# board_final.net
KiCad netlist of a schematic drawn in EAGLE
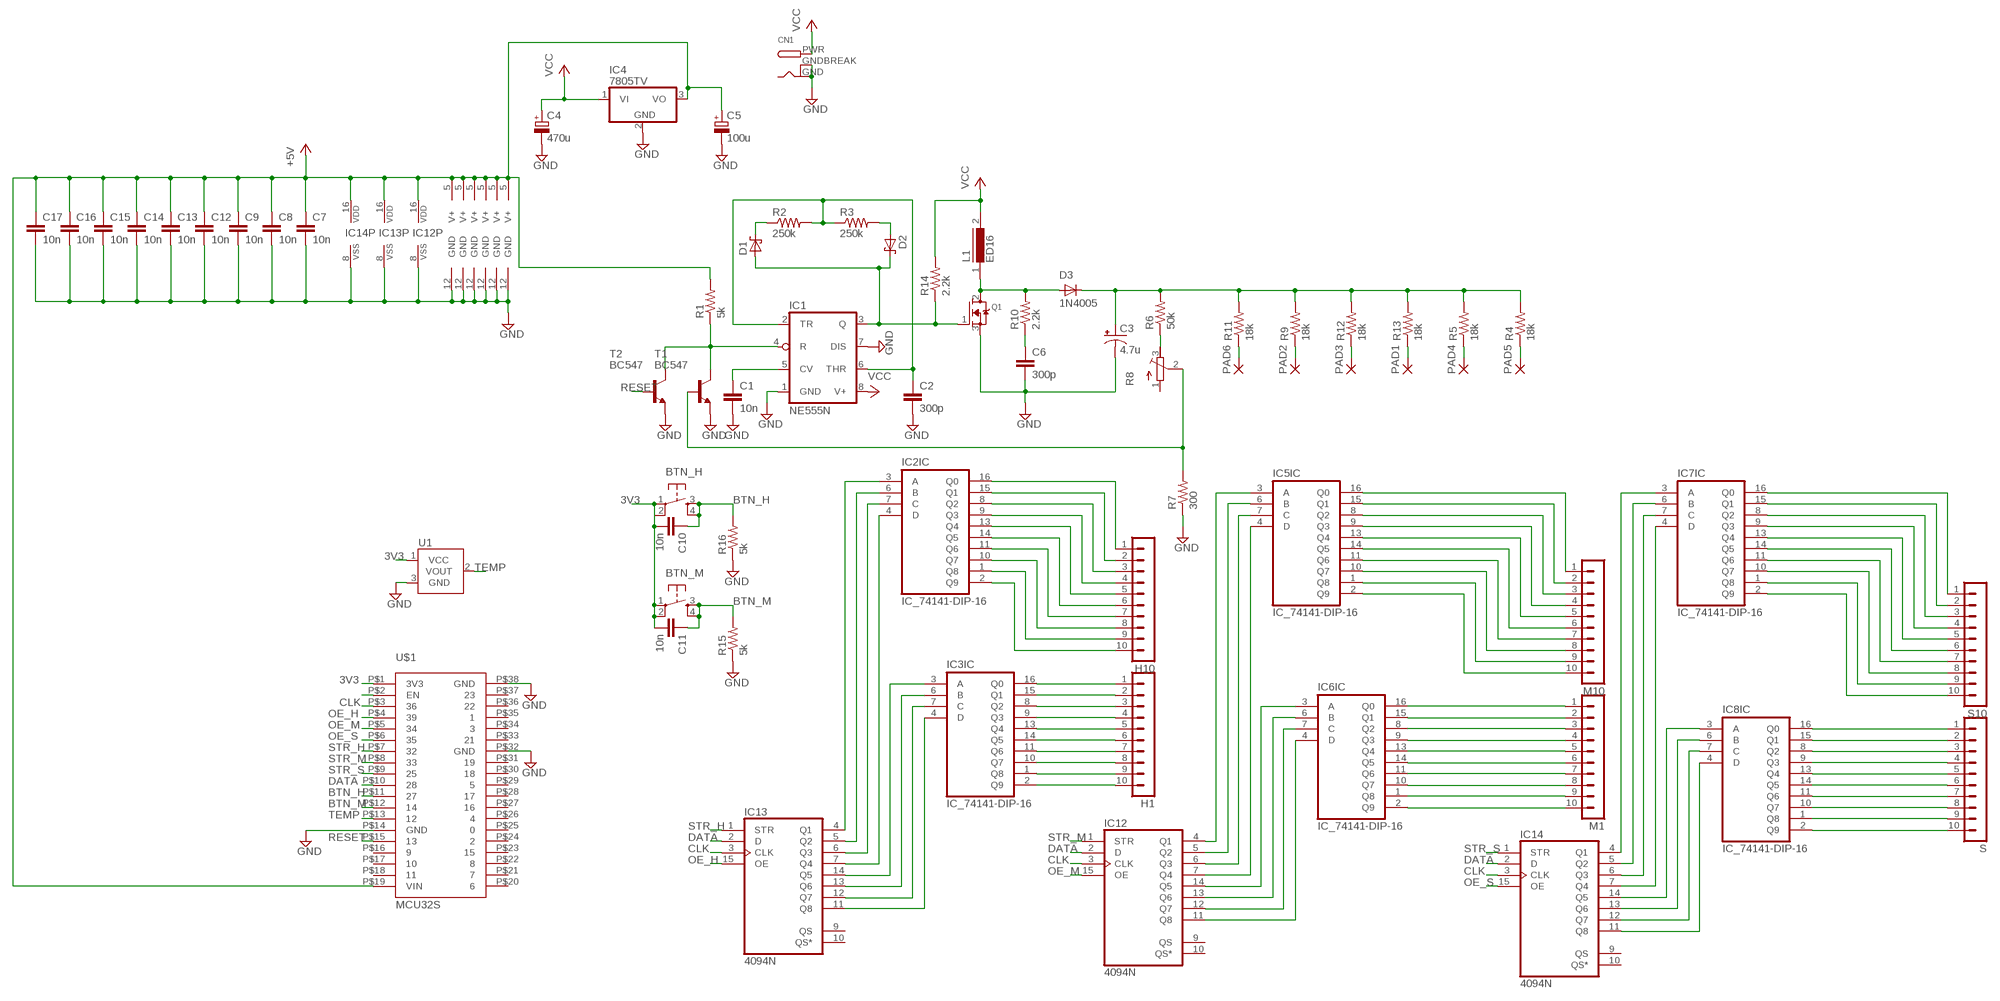
[diagram p0: schematic, sheet 1]

(export (version "E")
  (design (tool "Eeschema 10.0.6"))
  (components
    (comp (ref "BTN_H")
      (value "TAC_SWITCHPTH")
      (footprint "eagle-import:TACTILE-PTH")
      (libsource (lib "eagle-import") (part "TAC_SWITCHPTH"))
    )
    (comp (ref "BTN_M")
      (value "TAC_SWITCHPTH")
      (footprint "eagle-import:TACTILE-PTH")
      (libsource (lib "eagle-import") (part "TAC_SWITCHPTH"))
    )
    (comp (ref "C1")
      (value "10n")
      (footprint "eagle-import:C050-030X075")
      (libsource (lib "eagle-import") (part "C-EU050-030X075"))
    )
    (comp (ref "C2")
      (value "300p")
      (footprint "eagle-import:C050-030X075")
      (libsource (lib "eagle-import") (part "C-EU050-030X075"))
    )
    (comp (ref "C3")
      (value "4.7u")
      (footprint "eagle-import:E3,5-10")
      (libsource (lib "eagle-import") (part "CPOL-USE3.5-10"))
    )
    (comp (ref "C4")
      (value "470u")
      (footprint "eagle-import:E5-8,5")
      (libsource (lib "eagle-import") (part "CPOL-EUE5-8.5"))
    )
    (comp (ref "C5")
      (value "100u")
      (footprint "eagle-import:E5-8,5")
      (libsource (lib "eagle-import") (part "CPOL-EUE5-8.5"))
    )
    (comp (ref "C6")
      (value "300p")
      (footprint "eagle-import:C050-030X075")
      (libsource (lib "eagle-import") (part "C-EU050-030X075"))
    )
    (comp (ref "C7")
      (value "10n")
      (footprint "eagle-import:C050-030X075")
      (libsource (lib "eagle-import") (part "C-EU050-030X075"))
    )
    (comp (ref "C8")
      (value "10n")
      (footprint "eagle-import:C050-030X075")
      (libsource (lib "eagle-import") (part "C-EU050-030X075"))
    )
    (comp (ref "C9")
      (value "10n")
      (footprint "eagle-import:C050-030X075")
      (libsource (lib "eagle-import") (part "C-EU050-030X075"))
    )
    (comp (ref "C10")
      (value "10n")
      (footprint "eagle-import:C050-030X075")
      (libsource (lib "eagle-import") (part "C-EU050-030X075"))
    )
    (comp (ref "C11")
      (value "10n")
      (footprint "eagle-import:C050-030X075")
      (libsource (lib "eagle-import") (part "C-EU050-030X075"))
    )
    (comp (ref "C12")
      (value "10n")
      (footprint "eagle-import:C050-030X075")
      (libsource (lib "eagle-import") (part "C-EU050-030X075"))
    )
    (comp (ref "C13")
      (value "10n")
      (footprint "eagle-import:C050-030X075")
      (libsource (lib "eagle-import") (part "C-EU050-030X075"))
    )
    (comp (ref "C14")
      (value "10n")
      (footprint "eagle-import:C050-030X075")
      (libsource (lib "eagle-import") (part "C-EU050-030X075"))
    )
    (comp (ref "C15")
      (value "10n")
      (footprint "eagle-import:C050-030X075")
      (libsource (lib "eagle-import") (part "C-EU050-030X075"))
    )
    (comp (ref "C16")
      (value "10n")
      (footprint "eagle-import:C050-030X075")
      (libsource (lib "eagle-import") (part "C-EU050-030X075"))
    )
    (comp (ref "C17")
      (value "10n")
      (footprint "eagle-import:C050-030X075")
      (libsource (lib "eagle-import") (part "C-EU050-030X075"))
    )
    (comp (ref "CN1")
      (value "DCBARRELPTH")
      (footprint "eagle-import:DCJACK_2MM_PTH")
      (libsource (lib "eagle-import") (part "DCBARRELPTH"))
    )
    (comp (ref "D1")
      (value "SCHOTTKY-DIODEF126Z12")
      (footprint "eagle-import:F126Z12")
      (libsource (lib "eagle-import") (part "SCHOTTKY-DIODEF126Z12"))
    )
    (comp (ref "D2")
      (value "SCHOTTKY-DIODEF126Z12")
      (footprint "eagle-import:F126Z12")
      (libsource (lib "eagle-import") (part "SCHOTTKY-DIODEF126Z12"))
    )
    (comp (ref "D3")
      (value "1N4005")
      (footprint "eagle-import:DO41-10")
      (libsource (lib "eagle-import") (part "1N4005"))
    )
    (comp (ref "H1")
      (value "MA10-1")
      (footprint "eagle-import:MA10-1")
      (libsource (lib "eagle-import") (part "MA10-1"))
    )
    (comp (ref "H10")
      (value "MA10-1")
      (footprint "eagle-import:MA10-1")
      (libsource (lib "eagle-import") (part "MA10-1"))
    )
    (comp (ref "IC1")
      (value "NE555N")
      (footprint "eagle-import:DIL08")
      (libsource (lib "eagle-import") (part "555NNE"))
    )
    (comp (ref "IC2")
      (value "IC_74141-DIP-16")
      (footprint "eagle-import:DIL16")
      (libsource (lib "eagle-import") (part "IC_74141-DIP-16"))
    )
    (comp (ref "IC3")
      (value "IC_74141-DIP-16")
      (footprint "eagle-import:DIL16")
      (libsource (lib "eagle-import") (part "IC_74141-DIP-16"))
    )
    (comp (ref "IC4")
      (value "7805TV")
      (footprint "eagle-import:TO220V")
      (libsource (lib "eagle-import") (part "78TV05"))
    )
    (comp (ref "IC5")
      (value "IC_74141-DIP-16")
      (footprint "eagle-import:DIL16")
      (libsource (lib "eagle-import") (part "IC_74141-DIP-16"))
    )
    (comp (ref "IC6")
      (value "IC_74141-DIP-16")
      (footprint "eagle-import:DIL16")
      (libsource (lib "eagle-import") (part "IC_74141-DIP-16"))
    )
    (comp (ref "IC7")
      (value "IC_74141-DIP-16")
      (footprint "eagle-import:DIL16")
      (libsource (lib "eagle-import") (part "IC_74141-DIP-16"))
    )
    (comp (ref "IC8")
      (value "IC_74141-DIP-16")
      (footprint "eagle-import:DIL16")
      (libsource (lib "eagle-import") (part "IC_74141-DIP-16"))
    )
    (comp (ref "IC12")
      (value "4094N")
      (footprint "eagle-import:DIL16")
      (libsource (lib "eagle-import") (part "4094N"))
    )
    (comp (ref "IC13")
      (value "4094N")
      (footprint "eagle-import:DIL16")
      (libsource (lib "eagle-import") (part "4094N"))
    )
    (comp (ref "IC14")
      (value "4094N")
      (footprint "eagle-import:DIL16")
      (libsource (lib "eagle-import") (part "4094N"))
    )
    (comp (ref "L1")
      (value "ED16")
      (footprint "eagle-import:ED16")
      (libsource (lib "eagle-import") (part "ED16"))
    )
    (comp (ref "M1")
      (value "MA10-1")
      (footprint "eagle-import:MA10-1")
      (libsource (lib "eagle-import") (part "MA10-1"))
    )
    (comp (ref "M10")
      (value "MA10-1")
      (footprint "eagle-import:MA10-1")
      (libsource (lib "eagle-import") (part "MA10-1"))
    )
    (comp (ref "PAD1")
      (value "3,17/1,3")
      (footprint "eagle-import:3,17_1,3")
      (libsource (lib "eagle-import") (part "3,17/1,3"))
    )
    (comp (ref "PAD2")
      (value "3,17/1,3")
      (footprint "eagle-import:3,17_1,3")
      (libsource (lib "eagle-import") (part "3,17/1,3"))
    )
    (comp (ref "PAD3")
      (value "3,17/1,3")
      (footprint "eagle-import:3,17_1,3")
      (libsource (lib "eagle-import") (part "3,17/1,3"))
    )
    (comp (ref "PAD4")
      (value "3,17/1,3")
      (footprint "eagle-import:3,17_1,3")
      (libsource (lib "eagle-import") (part "3,17/1,3"))
    )
    (comp (ref "PAD5")
      (value "3,17/1,3")
      (footprint "eagle-import:3,17_1,3")
      (libsource (lib "eagle-import") (part "3,17/1,3"))
    )
    (comp (ref "PAD6")
      (value "3,17/1,3")
      (footprint "eagle-import:3,17_1,3")
      (libsource (lib "eagle-import") (part "3,17/1,3"))
    )
    (comp (ref "Q1")
      (value "MOSFET-NGDS_TO220V")
      (footprint "eagle-import:TO220V")
      (libsource (lib "eagle-import") (part "MOSFET-NGDS_TO220V"))
    )
    (comp (ref "R1")
      (value "5k")
      (footprint "eagle-import:0207_10")
      (libsource (lib "eagle-import") (part "R-US_0207/10"))
    )
    (comp (ref "R2")
      (value "250k")
      (footprint "eagle-import:0207_10")
      (libsource (lib "eagle-import") (part "R-US_0207/10"))
    )
    (comp (ref "R3")
      (value "250k")
      (footprint "eagle-import:0207_10")
      (libsource (lib "eagle-import") (part "R-US_0207/10"))
    )
    (comp (ref "R4")
      (value "18k")
      (footprint "eagle-import:0207_10")
      (libsource (lib "eagle-import") (part "R-US_0207/10"))
    )
    (comp (ref "R5")
      (value "18k")
      (footprint "eagle-import:0207_10")
      (libsource (lib "eagle-import") (part "R-US_0207/10"))
    )
    (comp (ref "R6")
      (value "50k")
      (footprint "eagle-import:0207_10")
      (libsource (lib "eagle-import") (part "R-US_0207/10"))
    )
    (comp (ref "R7")
      (value "300")
      (footprint "eagle-import:0207_10")
      (libsource (lib "eagle-import") (part "R-US_0207/10"))
    )
    (comp (ref "R8")
      (value "R-TRIMM3296W")
      (footprint "eagle-import:RTRIM3296W")
      (libsource (lib "eagle-import") (part "R-TRIMM3296W"))
    )
    (comp (ref "R9")
      (value "18k")
      (footprint "eagle-import:0207_10")
      (libsource (lib "eagle-import") (part "R-US_0207/10"))
    )
    (comp (ref "R10")
      (value "2.2k")
      (footprint "eagle-import:0207_10")
      (libsource (lib "eagle-import") (part "R-US_0207/10"))
    )
    (comp (ref "R11")
      (value "18k")
      (footprint "eagle-import:0207_10")
      (libsource (lib "eagle-import") (part "R-US_0207/10"))
    )
    (comp (ref "R12")
      (value "18k")
      (footprint "eagle-import:0207_10")
      (libsource (lib "eagle-import") (part "R-US_0207/10"))
    )
    (comp (ref "R13")
      (value "18k")
      (footprint "eagle-import:0207_10")
      (libsource (lib "eagle-import") (part "R-US_0207/10"))
    )
    (comp (ref "R14")
      (value "2.2k")
      (footprint "eagle-import:0207_10")
      (libsource (lib "eagle-import") (part "R-US_0207/10"))
    )
    (comp (ref "R15")
      (value "5k")
      (footprint "eagle-import:0207_10")
      (libsource (lib "eagle-import") (part "R-US_0207/10"))
    )
    (comp (ref "R16")
      (value "5k")
      (footprint "eagle-import:0207_10")
      (libsource (lib "eagle-import") (part "R-US_0207/10"))
    )
    (comp (ref "S")
      (value "MA10-1")
      (footprint "eagle-import:MA10-1")
      (libsource (lib "eagle-import") (part "MA10-1"))
    )
    (comp (ref "S10")
      (value "MA10-1")
      (footprint "eagle-import:MA10-1")
      (libsource (lib "eagle-import") (part "MA10-1"))
    )
    (comp (ref "T1")
      (value "BC547")
      (footprint "eagle-import:TO92")
      (libsource (lib "eagle-import") (part "BC547"))
    )
    (comp (ref "T2")
      (value "BC547")
      (footprint "eagle-import:TO92")
      (libsource (lib "eagle-import") (part "BC547"))
    )
    (comp (ref "U$1")
      (value "MCU32S")
      (footprint "eagle-import:NODEMCU32S")
      (libsource (lib "eagle-import") (part "MCU32S"))
    )
    (comp (ref "U1")
      (value "TMP36GT9")
      (footprint "eagle-import:TO-92")
      (libsource (lib "eagle-import") (part "TMP36GT9"))
    )
  )
  (nets
    (net (code "1") (name "+5V") (class "Default")
      (node (ref "C12") (pin "1") (pinfunction "1_1") (pintype "passive"))
      (node (ref "C13") (pin "1") (pinfunction "1_1") (pintype "passive"))
      (node (ref "C14") (pin "1") (pinfunction "1_1") (pintype "passive"))
      (node (ref "C15") (pin "1") (pinfunction "1_1") (pintype "passive"))
      (node (ref "C16") (pin "1") (pinfunction "1_1") (pintype "passive"))
      (node (ref "C17") (pin "1") (pinfunction "1_1") (pintype "passive"))
      (node (ref "C5") (pin "+") (pinfunction "+_+") (pintype "passive"))
      (node (ref "C7") (pin "1") (pinfunction "1_1") (pintype "passive"))
      (node (ref "C8") (pin "1") (pinfunction "1_1") (pintype "passive"))
      (node (ref "C9") (pin "1") (pinfunction "1_1") (pintype "passive"))
      (node (ref "IC12") (pin "16") (pinfunction "VDD_16") (pintype "power_in"))
      (node (ref "IC13") (pin "16") (pinfunction "VDD_16") (pintype "power_in"))
      (node (ref "IC14") (pin "16") (pinfunction "VDD_16") (pintype "power_in"))
      (node (ref "IC2") (pin "5") (pinfunction "V+_5") (pintype "power_in"))
      (node (ref "IC3") (pin "5") (pinfunction "V+_5") (pintype "power_in"))
      (node (ref "IC4") (pin "3") (pinfunction "VO_3") (pintype "passive"))
      (node (ref "IC5") (pin "5") (pinfunction "V+_5") (pintype "power_in"))
      (node (ref "IC6") (pin "5") (pinfunction "V+_5") (pintype "power_in"))
      (node (ref "IC7") (pin "5") (pinfunction "V+_5") (pintype "power_in"))
      (node (ref "IC8") (pin "5") (pinfunction "V+_5") (pintype "power_in"))
      (node (ref "R1") (pin "2") (pinfunction "2_2") (pintype "passive"))
      (node (ref "U$1") (pin "P$19") (pinfunction "VIN_P$19") (pintype "bidirectional"))
    )
    (net (code "2") (name "/3V3") (class "Default")
      (node (ref "BTN_H") (pin "1") (pinfunction "1_1") (pintype "passive"))
      (node (ref "BTN_H") (pin "2") (pinfunction "2_2") (pintype "passive"))
      (node (ref "BTN_M") (pin "1") (pinfunction "1_1") (pintype "passive"))
      (node (ref "BTN_M") (pin "2") (pinfunction "2_2") (pintype "passive"))
      (node (ref "C10") (pin "2") (pinfunction "2_2") (pintype "passive"))
      (node (ref "C11") (pin "2") (pinfunction "2_2") (pintype "passive"))
      (node (ref "U$1") (pin "P$1") (pinfunction "3V3_P$1") (pintype "bidirectional"))
      (node (ref "U1") (pin "1") (pinfunction "VCC_1") (pintype "bidirectional"))
    )
    (net (code "3") (name "/BTN_H") (class "Default")
      (node (ref "BTN_H") (pin "3") (pinfunction "3_3") (pintype "passive"))
      (node (ref "BTN_H") (pin "4") (pinfunction "4_4") (pintype "passive"))
      (node (ref "C10") (pin "1") (pinfunction "1_1") (pintype "passive"))
      (node (ref "R16") (pin "2") (pinfunction "2_2") (pintype "passive"))
      (node (ref "U$1") (pin "P$11") (pinfunction "27_P$11") (pintype "bidirectional"))
    )
    (net (code "4") (name "/BTN_M") (class "Default")
      (node (ref "BTN_M") (pin "3") (pinfunction "3_3") (pintype "passive"))
      (node (ref "BTN_M") (pin "4") (pinfunction "4_4") (pintype "passive"))
      (node (ref "C11") (pin "1") (pinfunction "1_1") (pintype "passive"))
      (node (ref "R15") (pin "2") (pinfunction "2_2") (pintype "passive"))
      (node (ref "U$1") (pin "P$12") (pinfunction "14_P$12") (pintype "bidirectional"))
    )
    (net (code "5") (name "/CLK") (class "Default")
      (node (ref "IC12") (pin "3") (pinfunction "CLK_3") (pintype "input"))
      (node (ref "IC13") (pin "3") (pinfunction "CLK_3") (pintype "input"))
      (node (ref "IC14") (pin "3") (pinfunction "CLK_3") (pintype "input"))
      (node (ref "U$1") (pin "P$3") (pinfunction "36_P$3") (pintype "bidirectional"))
    )
    (net (code "6") (name "/DATA") (class "Default")
      (node (ref "IC12") (pin "2") (pinfunction "D_2") (pintype "input"))
      (node (ref "IC13") (pin "2") (pinfunction "D_2") (pintype "input"))
      (node (ref "IC14") (pin "2") (pinfunction "D_2") (pintype "input"))
      (node (ref "U$1") (pin "P$10") (pinfunction "28_P$10") (pintype "bidirectional"))
    )
    (net (code "7") (name "/OE_H") (class "Default")
      (node (ref "IC13") (pin "15") (pinfunction "OE_15") (pintype "input"))
      (node (ref "U$1") (pin "P$4") (pinfunction "39_P$4") (pintype "bidirectional"))
    )
    (net (code "8") (name "/OE_M") (class "Default")
      (node (ref "IC12") (pin "15") (pinfunction "OE_15") (pintype "input"))
      (node (ref "U$1") (pin "P$5") (pinfunction "34_P$5") (pintype "bidirectional"))
    )
    (net (code "9") (name "/OE_S") (class "Default")
      (node (ref "IC14") (pin "15") (pinfunction "OE_15") (pintype "input"))
      (node (ref "U$1") (pin "P$6") (pinfunction "35_P$6") (pintype "bidirectional"))
    )
    (net (code "10") (name "/RESET") (class "Default")
      (node (ref "T2") (pin "2") (pinfunction "B_2") (pintype "passive"))
      (node (ref "U$1") (pin "P$15") (pinfunction "13_P$15") (pintype "bidirectional"))
    )
    (net (code "11") (name "/STR_H") (class "Default")
      (node (ref "IC13") (pin "1") (pinfunction "STR_1") (pintype "input"))
      (node (ref "U$1") (pin "P$7") (pinfunction "32_P$7") (pintype "bidirectional"))
    )
    (net (code "12") (name "/STR_M") (class "Default")
      (node (ref "IC12") (pin "1") (pinfunction "STR_1") (pintype "input"))
      (node (ref "U$1") (pin "P$8") (pinfunction "33_P$8") (pintype "bidirectional"))
    )
    (net (code "13") (name "/STR_S") (class "Default")
      (node (ref "IC14") (pin "1") (pinfunction "STR_1") (pintype "input"))
      (node (ref "U$1") (pin "P$9") (pinfunction "25_P$9") (pintype "bidirectional"))
    )
    (net (code "14") (name "/TEMP") (class "Default")
      (node (ref "U$1") (pin "P$13") (pinfunction "12_P$13") (pintype "bidirectional"))
      (node (ref "U1") (pin "2") (pinfunction "VOUT_2") (pintype "bidirectional"))
    )
    (net (code "15") (name "GND") (class "Default")
      (node (ref "C1") (pin "2") (pinfunction "2_2") (pintype "passive"))
      (node (ref "C12") (pin "2") (pinfunction "2_2") (pintype "passive"))
      (node (ref "C13") (pin "2") (pinfunction "2_2") (pintype "passive"))
      (node (ref "C14") (pin "2") (pinfunction "2_2") (pintype "passive"))
      (node (ref "C15") (pin "2") (pinfunction "2_2") (pintype "passive"))
      (node (ref "C16") (pin "2") (pinfunction "2_2") (pintype "passive"))
      (node (ref "C17") (pin "2") (pinfunction "2_2") (pintype "passive"))
      (node (ref "C2") (pin "2") (pinfunction "2_2") (pintype "passive"))
      (node (ref "C3") (pin "-") (pinfunction "-_-") (pintype "passive"))
      (node (ref "C4") (pin "-") (pinfunction "-_-") (pintype "passive"))
      (node (ref "C5") (pin "-") (pinfunction "-_-") (pintype "passive"))
      (node (ref "C6") (pin "2") (pinfunction "2_2") (pintype "passive"))
      (node (ref "C7") (pin "2") (pinfunction "2_2") (pintype "passive"))
      (node (ref "C8") (pin "2") (pinfunction "2_2") (pintype "passive"))
      (node (ref "C9") (pin "2") (pinfunction "2_2") (pintype "passive"))
      (node (ref "CN1") (pin "GND") (pinfunction "GND_GND") (pintype "power_in"))
      (node (ref "CN1") (pin "GNDBREAK") (pinfunction "GNDBREAK_GNDBREAK") (pintype "power_in"))
      (node (ref "IC1") (pin "1") (pinfunction "GND_1") (pintype "power_in"))
      (node (ref "IC1") (pin "7") (pinfunction "DIS_7") (pintype "input"))
      (node (ref "IC12") (pin "8") (pinfunction "VSS_8") (pintype "power_in"))
      (node (ref "IC13") (pin "8") (pinfunction "VSS_8") (pintype "power_in"))
      (node (ref "IC14") (pin "8") (pinfunction "VSS_8") (pintype "power_in"))
      (node (ref "IC2") (pin "12") (pinfunction "GND_12") (pintype "power_in"))
      (node (ref "IC3") (pin "12") (pinfunction "GND_12") (pintype "power_in"))
      (node (ref "IC4") (pin "2") (pinfunction "GND_2") (pintype "passive"))
      (node (ref "IC5") (pin "12") (pinfunction "GND_12") (pintype "power_in"))
      (node (ref "IC6") (pin "12") (pinfunction "GND_12") (pintype "power_in"))
      (node (ref "IC7") (pin "12") (pinfunction "GND_12") (pintype "power_in"))
      (node (ref "IC8") (pin "12") (pinfunction "GND_12") (pintype "power_in"))
      (node (ref "Q1") (pin "3") (pinfunction "S_3") (pintype "bidirectional"))
      (node (ref "R15") (pin "1") (pinfunction "1_1") (pintype "passive"))
      (node (ref "R16") (pin "1") (pinfunction "1_1") (pintype "passive"))
      (node (ref "R7") (pin "1") (pinfunction "1_1") (pintype "passive"))
      (node (ref "T1") (pin "1") (pinfunction "E_1") (pintype "passive"))
      (node (ref "T2") (pin "1") (pinfunction "E_1") (pintype "passive"))
      (node (ref "U$1") (pin "P$14") (pinfunction "GND_P$14") (pintype "bidirectional"))
      (node (ref "U$1") (pin "P$32") (pinfunction "GND_P$32") (pintype "bidirectional"))
      (node (ref "U$1") (pin "P$38") (pinfunction "GND_P$38") (pintype "bidirectional"))
      (node (ref "U1") (pin "3") (pinfunction "GND_3") (pintype "bidirectional"))
    )
    (net (code "16") (name "Net-(C3-Pad+)") (class "Default")
      (node (ref "C3") (pin "+") (pinfunction "+_+") (pintype "passive"))
      (node (ref "D3") (pin "C") (pinfunction "C_C") (pintype "passive"))
      (node (ref "R11") (pin "2") (pinfunction "2_2") (pintype "passive"))
      (node (ref "R12") (pin "2") (pinfunction "2_2") (pintype "passive"))
      (node (ref "R13") (pin "2") (pinfunction "2_2") (pintype "passive"))
      (node (ref "R4") (pin "2") (pinfunction "2_2") (pintype "passive"))
      (node (ref "R5") (pin "2") (pinfunction "2_2") (pintype "passive"))
      (node (ref "R6") (pin "2") (pinfunction "2_2") (pintype "passive"))
      (node (ref "R9") (pin "2") (pinfunction "2_2") (pintype "passive"))
    )
    (net (code "17") (name "Net-(C6-Pad1)") (class "Default")
      (node (ref "C6") (pin "1") (pinfunction "1_1") (pintype "passive"))
      (node (ref "R10") (pin "1") (pinfunction "1_1") (pintype "passive"))
    )
    (net (code "18") (name "Net-(D1-PadC)") (class "Default")
      (node (ref "D1") (pin "C") (pinfunction "C_C") (pintype "passive"))
      (node (ref "R2") (pin "1") (pinfunction "1_1") (pintype "passive"))
    )
    (net (code "19") (name "Net-(D2-PadA)") (class "Default")
      (node (ref "D2") (pin "A") (pinfunction "A_A") (pintype "passive"))
      (node (ref "R3") (pin "2") (pinfunction "2_2") (pintype "passive"))
    )
    (net (code "20") (name "Net-(IC1-CV)") (class "Default")
      (node (ref "C1") (pin "1") (pinfunction "1_1") (pintype "passive"))
      (node (ref "IC1") (pin "5") (pinfunction "CV_5") (pintype "input"))
    )
    (net (code "21") (name "Net-(IC1-Q)") (class "Default")
      (node (ref "D1") (pin "A") (pinfunction "A_A") (pintype "passive"))
      (node (ref "D2") (pin "C") (pinfunction "C_C") (pintype "passive"))
      (node (ref "IC1") (pin "3") (pinfunction "Q_3") (pintype "output"))
      (node (ref "Q1") (pin "1") (pinfunction "G_1") (pintype "bidirectional"))
      (node (ref "R14") (pin "1") (pinfunction "1_1") (pintype "passive"))
    )
    (net (code "22") (name "Net-(IC1-R)") (class "Default")
      (node (ref "IC1") (pin "4") (pinfunction "R_4") (pintype "input"))
      (node (ref "R1") (pin "1") (pinfunction "1_1") (pintype "passive"))
      (node (ref "T1") (pin "3") (pinfunction "C_3") (pintype "passive"))
      (node (ref "T2") (pin "3") (pinfunction "C_3") (pintype "passive"))
    )
    (net (code "23") (name "Net-(IC1-THR)") (class "Default")
      (node (ref "C2") (pin "1") (pinfunction "1_1") (pintype "passive"))
      (node (ref "IC1") (pin "2") (pinfunction "TR_2") (pintype "input"))
      (node (ref "IC1") (pin "6") (pinfunction "THR_6") (pintype "input"))
      (node (ref "R2") (pin "2") (pinfunction "2_2") (pintype "passive"))
      (node (ref "R3") (pin "1") (pinfunction "1_1") (pintype "passive"))
    )
    (net (code "24") (name "Net-(IC2A-Q0)") (class "Default")
      (node (ref "H10") (pin "1") (pinfunction "1_1") (pintype "passive"))
      (node (ref "IC2") (pin "16") (pinfunction "Q0_16") (pintype "output"))
    )
    (net (code "25") (name "Net-(IC2A-Q1)") (class "Default")
      (node (ref "H10") (pin "2") (pinfunction "2_2") (pintype "passive"))
      (node (ref "IC2") (pin "15") (pinfunction "Q1_15") (pintype "output"))
    )
    (net (code "26") (name "Net-(IC2A-Q2)") (class "Default")
      (node (ref "H10") (pin "3") (pinfunction "3_3") (pintype "passive"))
      (node (ref "IC2") (pin "8") (pinfunction "Q2_8") (pintype "output"))
    )
    (net (code "27") (name "Net-(IC2A-Q3)") (class "Default")
      (node (ref "H10") (pin "4") (pinfunction "4_4") (pintype "passive"))
      (node (ref "IC2") (pin "9") (pinfunction "Q3_9") (pintype "output"))
    )
    (net (code "28") (name "Net-(IC2A-Q4)") (class "Default")
      (node (ref "H10") (pin "5") (pinfunction "5_5") (pintype "passive"))
      (node (ref "IC2") (pin "13") (pinfunction "Q4_13") (pintype "output"))
    )
    (net (code "29") (name "Net-(IC2A-Q5)") (class "Default")
      (node (ref "H10") (pin "6") (pinfunction "6_6") (pintype "passive"))
      (node (ref "IC2") (pin "14") (pinfunction "Q5_14") (pintype "output"))
    )
    (net (code "30") (name "Net-(IC2A-Q6)") (class "Default")
      (node (ref "H10") (pin "7") (pinfunction "7_7") (pintype "passive"))
      (node (ref "IC2") (pin "11") (pinfunction "Q6_11") (pintype "output"))
    )
    (net (code "31") (name "Net-(IC2A-Q7)") (class "Default")
      (node (ref "H10") (pin "8") (pinfunction "8_8") (pintype "passive"))
      (node (ref "IC2") (pin "10") (pinfunction "Q7_10") (pintype "output"))
    )
    (net (code "32") (name "Net-(IC2A-Q8)") (class "Default")
      (node (ref "H10") (pin "9") (pinfunction "9_9") (pintype "passive"))
      (node (ref "IC2") (pin "1") (pinfunction "Q8_1") (pintype "output"))
    )
    (net (code "33") (name "Net-(IC2A-Q9)") (class "Default")
      (node (ref "H10") (pin "10") (pinfunction "10_10") (pintype "passive"))
      (node (ref "IC2") (pin "2") (pinfunction "Q9_2") (pintype "output"))
    )
    (net (code "34") (name "Net-(IC3A-Q0)") (class "Default")
      (node (ref "H1") (pin "1") (pinfunction "1_1") (pintype "passive"))
      (node (ref "IC3") (pin "16") (pinfunction "Q0_16") (pintype "output"))
    )
    (net (code "35") (name "Net-(IC3A-Q1)") (class "Default")
      (node (ref "H1") (pin "2") (pinfunction "2_2") (pintype "passive"))
      (node (ref "IC3") (pin "15") (pinfunction "Q1_15") (pintype "output"))
    )
    (net (code "36") (name "Net-(IC3A-Q2)") (class "Default")
      (node (ref "H1") (pin "3") (pinfunction "3_3") (pintype "passive"))
      (node (ref "IC3") (pin "8") (pinfunction "Q2_8") (pintype "output"))
    )
    (net (code "37") (name "Net-(IC3A-Q3)") (class "Default")
      (node (ref "H1") (pin "4") (pinfunction "4_4") (pintype "passive"))
      (node (ref "IC3") (pin "9") (pinfunction "Q3_9") (pintype "output"))
    )
    (net (code "38") (name "Net-(IC3A-Q4)") (class "Default")
      (node (ref "H1") (pin "5") (pinfunction "5_5") (pintype "passive"))
      (node (ref "IC3") (pin "13") (pinfunction "Q4_13") (pintype "output"))
    )
    (net (code "39") (name "Net-(IC3A-Q5)") (class "Default")
      (node (ref "H1") (pin "6") (pinfunction "6_6") (pintype "passive"))
      (node (ref "IC3") (pin "14") (pinfunction "Q5_14") (pintype "output"))
    )
    (net (code "40") (name "Net-(IC3A-Q6)") (class "Default")
      (node (ref "H1") (pin "7") (pinfunction "7_7") (pintype "passive"))
      (node (ref "IC3") (pin "11") (pinfunction "Q6_11") (pintype "output"))
    )
    (net (code "41") (name "Net-(IC3A-Q7)") (class "Default")
      (node (ref "H1") (pin "8") (pinfunction "8_8") (pintype "passive"))
      (node (ref "IC3") (pin "10") (pinfunction "Q7_10") (pintype "output"))
    )
    (net (code "42") (name "Net-(IC3A-Q8)") (class "Default")
      (node (ref "H1") (pin "9") (pinfunction "9_9") (pintype "passive"))
      (node (ref "IC3") (pin "1") (pinfunction "Q8_1") (pintype "output"))
    )
    (net (code "43") (name "Net-(IC3A-Q9)") (class "Default")
      (node (ref "H1") (pin "10") (pinfunction "10_10") (pintype "passive"))
      (node (ref "IC3") (pin "2") (pinfunction "Q9_2") (pintype "output"))
    )
    (net (code "44") (name "Net-(IC5A-Q0)") (class "Default")
      (node (ref "IC5") (pin "16") (pinfunction "Q0_16") (pintype "output"))
      (node (ref "M10") (pin "1") (pinfunction "1_1") (pintype "passive"))
    )
    (net (code "45") (name "Net-(IC5A-Q1)") (class "Default")
      (node (ref "IC5") (pin "15") (pinfunction "Q1_15") (pintype "output"))
      (node (ref "M10") (pin "2") (pinfunction "2_2") (pintype "passive"))
    )
    (net (code "46") (name "Net-(IC5A-Q2)") (class "Default")
      (node (ref "IC5") (pin "8") (pinfunction "Q2_8") (pintype "output"))
      (node (ref "M10") (pin "3") (pinfunction "3_3") (pintype "passive"))
    )
    (net (code "47") (name "Net-(IC5A-Q3)") (class "Default")
      (node (ref "IC5") (pin "9") (pinfunction "Q3_9") (pintype "output"))
      (node (ref "M10") (pin "4") (pinfunction "4_4") (pintype "passive"))
    )
    (net (code "48") (name "Net-(IC5A-Q4)") (class "Default")
      (node (ref "IC5") (pin "13") (pinfunction "Q4_13") (pintype "output"))
      (node (ref "M10") (pin "5") (pinfunction "5_5") (pintype "passive"))
    )
    (net (code "49") (name "Net-(IC5A-Q5)") (class "Default")
      (node (ref "IC5") (pin "14") (pinfunction "Q5_14") (pintype "output"))
      (node (ref "M10") (pin "6") (pinfunction "6_6") (pintype "passive"))
    )
    (net (code "50") (name "Net-(IC5A-Q6)") (class "Default")
      (node (ref "IC5") (pin "11") (pinfunction "Q6_11") (pintype "output"))
      (node (ref "M10") (pin "7") (pinfunction "7_7") (pintype "passive"))
    )
    (net (code "51") (name "Net-(IC5A-Q7)") (class "Default")
      (node (ref "IC5") (pin "10") (pinfunction "Q7_10") (pintype "output"))
      (node (ref "M10") (pin "8") (pinfunction "8_8") (pintype "passive"))
    )
    (net (code "52") (name "Net-(IC5A-Q8)") (class "Default")
      (node (ref "IC5") (pin "1") (pinfunction "Q8_1") (pintype "output"))
      (node (ref "M10") (pin "9") (pinfunction "9_9") (pintype "passive"))
    )
    (net (code "53") (name "Net-(IC5A-Q9)") (class "Default")
      (node (ref "IC5") (pin "2") (pinfunction "Q9_2") (pintype "output"))
      (node (ref "M10") (pin "10") (pinfunction "10_10") (pintype "passive"))
    )
    (net (code "54") (name "Net-(IC6A-Q0)") (class "Default")
      (node (ref "IC6") (pin "16") (pinfunction "Q0_16") (pintype "output"))
      (node (ref "M1") (pin "1") (pinfunction "1_1") (pintype "passive"))
    )
    (net (code "55") (name "Net-(IC6A-Q1)") (class "Default")
      (node (ref "IC6") (pin "15") (pinfunction "Q1_15") (pintype "output"))
      (node (ref "M1") (pin "2") (pinfunction "2_2") (pintype "passive"))
    )
    (net (code "56") (name "Net-(IC6A-Q2)") (class "Default")
      (node (ref "IC6") (pin "8") (pinfunction "Q2_8") (pintype "output"))
      (node (ref "M1") (pin "3") (pinfunction "3_3") (pintype "passive"))
    )
    (net (code "57") (name "Net-(IC6A-Q3)") (class "Default")
      (node (ref "IC6") (pin "9") (pinfunction "Q3_9") (pintype "output"))
      (node (ref "M1") (pin "4") (pinfunction "4_4") (pintype "passive"))
    )
    (net (code "58") (name "Net-(IC6A-Q4)") (class "Default")
      (node (ref "IC6") (pin "13") (pinfunction "Q4_13") (pintype "output"))
      (node (ref "M1") (pin "5") (pinfunction "5_5") (pintype "passive"))
    )
    (net (code "59") (name "Net-(IC6A-Q5)") (class "Default")
      (node (ref "IC6") (pin "14") (pinfunction "Q5_14") (pintype "output"))
      (node (ref "M1") (pin "6") (pinfunction "6_6") (pintype "passive"))
    )
    (net (code "60") (name "Net-(IC6A-Q6)") (class "Default")
      (node (ref "IC6") (pin "11") (pinfunction "Q6_11") (pintype "output"))
      (node (ref "M1") (pin "7") (pinfunction "7_7") (pintype "passive"))
    )
    (net (code "61") (name "Net-(IC6A-Q7)") (class "Default")
      (node (ref "IC6") (pin "10") (pinfunction "Q7_10") (pintype "output"))
      (node (ref "M1") (pin "8") (pinfunction "8_8") (pintype "passive"))
    )
    (net (code "62") (name "Net-(IC6A-Q8)") (class "Default")
      (node (ref "IC6") (pin "1") (pinfunction "Q8_1") (pintype "output"))
      (node (ref "M1") (pin "9") (pinfunction "9_9") (pintype "passive"))
    )
    (net (code "63") (name "Net-(IC6A-Q9)") (class "Default")
      (node (ref "IC6") (pin "2") (pinfunction "Q9_2") (pintype "output"))
      (node (ref "M1") (pin "10") (pinfunction "10_10") (pintype "passive"))
    )
    (net (code "64") (name "Net-(IC7A-Q0)") (class "Default")
      (node (ref "IC7") (pin "16") (pinfunction "Q0_16") (pintype "output"))
      (node (ref "S10") (pin "1") (pinfunction "1_1") (pintype "passive"))
    )
    (net (code "65") (name "Net-(IC7A-Q1)") (class "Default")
      (node (ref "IC7") (pin "15") (pinfunction "Q1_15") (pintype "output"))
      (node (ref "S10") (pin "2") (pinfunction "2_2") (pintype "passive"))
    )
    (net (code "66") (name "Net-(IC7A-Q2)") (class "Default")
      (node (ref "IC7") (pin "8") (pinfunction "Q2_8") (pintype "output"))
      (node (ref "S10") (pin "3") (pinfunction "3_3") (pintype "passive"))
    )
    (net (code "67") (name "Net-(IC7A-Q3)") (class "Default")
      (node (ref "IC7") (pin "9") (pinfunction "Q3_9") (pintype "output"))
      (node (ref "S10") (pin "4") (pinfunction "4_4") (pintype "passive"))
    )
    (net (code "68") (name "Net-(IC7A-Q4)") (class "Default")
      (node (ref "IC7") (pin "13") (pinfunction "Q4_13") (pintype "output"))
      (node (ref "S10") (pin "5") (pinfunction "5_5") (pintype "passive"))
    )
    (net (code "69") (name "Net-(IC7A-Q5)") (class "Default")
      (node (ref "IC7") (pin "14") (pinfunction "Q5_14") (pintype "output"))
      (node (ref "S10") (pin "6") (pinfunction "6_6") (pintype "passive"))
    )
    (net (code "70") (name "Net-(IC7A-Q6)") (class "Default")
      (node (ref "IC7") (pin "11") (pinfunction "Q6_11") (pintype "output"))
      (node (ref "S10") (pin "7") (pinfunction "7_7") (pintype "passive"))
    )
    (net (code "71") (name "Net-(IC7A-Q7)") (class "Default")
      (node (ref "IC7") (pin "10") (pinfunction "Q7_10") (pintype "output"))
      (node (ref "S10") (pin "8") (pinfunction "8_8") (pintype "passive"))
    )
    (net (code "72") (name "Net-(IC7A-Q8)") (class "Default")
      (node (ref "IC7") (pin "1") (pinfunction "Q8_1") (pintype "output"))
      (node (ref "S10") (pin "9") (pinfunction "9_9") (pintype "passive"))
    )
    (net (code "73") (name "Net-(IC7A-Q9)") (class "Default")
      (node (ref "IC7") (pin "2") (pinfunction "Q9_2") (pintype "output"))
      (node (ref "S10") (pin "10") (pinfunction "10_10") (pintype "passive"))
    )
    (net (code "74") (name "Net-(IC8A-Q0)") (class "Default")
      (node (ref "IC8") (pin "16") (pinfunction "Q0_16") (pintype "output"))
      (node (ref "S") (pin "1") (pinfunction "1_1") (pintype "passive"))
    )
    (net (code "75") (name "Net-(IC8A-Q1)") (class "Default")
      (node (ref "IC8") (pin "15") (pinfunction "Q1_15") (pintype "output"))
      (node (ref "S") (pin "2") (pinfunction "2_2") (pintype "passive"))
    )
    (net (code "76") (name "Net-(IC8A-Q2)") (class "Default")
      (node (ref "IC8") (pin "8") (pinfunction "Q2_8") (pintype "output"))
      (node (ref "S") (pin "3") (pinfunction "3_3") (pintype "passive"))
    )
    (net (code "77") (name "Net-(IC8A-Q3)") (class "Default")
      (node (ref "IC8") (pin "9") (pinfunction "Q3_9") (pintype "output"))
      (node (ref "S") (pin "4") (pinfunction "4_4") (pintype "passive"))
    )
    (net (code "78") (name "Net-(IC8A-Q4)") (class "Default")
      (node (ref "IC8") (pin "13") (pinfunction "Q4_13") (pintype "output"))
      (node (ref "S") (pin "5") (pinfunction "5_5") (pintype "passive"))
    )
    (net (code "79") (name "Net-(IC8A-Q5)") (class "Default")
      (node (ref "IC8") (pin "14") (pinfunction "Q5_14") (pintype "output"))
      (node (ref "S") (pin "6") (pinfunction "6_6") (pintype "passive"))
    )
    (net (code "80") (name "Net-(IC8A-Q6)") (class "Default")
      (node (ref "IC8") (pin "11") (pinfunction "Q6_11") (pintype "output"))
      (node (ref "S") (pin "7") (pinfunction "7_7") (pintype "passive"))
    )
    (net (code "81") (name "Net-(IC8A-Q7)") (class "Default")
      (node (ref "IC8") (pin "10") (pinfunction "Q7_10") (pintype "output"))
      (node (ref "S") (pin "8") (pinfunction "8_8") (pintype "passive"))
    )
    (net (code "82") (name "Net-(IC8A-Q8)") (class "Default")
      (node (ref "IC8") (pin "1") (pinfunction "Q8_1") (pintype "output"))
      (node (ref "S") (pin "9") (pinfunction "9_9") (pintype "passive"))
    )
    (net (code "83") (name "Net-(IC8A-Q9)") (class "Default")
      (node (ref "IC8") (pin "2") (pinfunction "Q9_2") (pintype "output"))
      (node (ref "S") (pin "10") (pinfunction "10_10") (pintype "passive"))
    )
    (net (code "84") (name "Net-(IC12A-Q1)") (class "Default")
      (node (ref "IC12") (pin "4") (pinfunction "Q1_4") (pintype "output"))
      (node (ref "IC5") (pin "3") (pinfunction "A_3") (pintype "input"))
    )
    (net (code "85") (name "Net-(IC12A-Q2)") (class "Default")
      (node (ref "IC12") (pin "5") (pinfunction "Q2_5") (pintype "output"))
      (node (ref "IC5") (pin "6") (pinfunction "B_6") (pintype "input"))
    )
    (net (code "86") (name "Net-(IC12A-Q3)") (class "Default")
      (node (ref "IC12") (pin "6") (pinfunction "Q3_6") (pintype "output"))
      (node (ref "IC5") (pin "7") (pinfunction "C_7") (pintype "input"))
    )
    (net (code "87") (name "Net-(IC12A-Q4)") (class "Default")
      (node (ref "IC12") (pin "7") (pinfunction "Q4_7") (pintype "output"))
      (node (ref "IC5") (pin "4") (pinfunction "D_4") (pintype "input"))
    )
    (net (code "88") (name "Net-(IC12A-Q5)") (class "Default")
      (node (ref "IC12") (pin "14") (pinfunction "Q5_14") (pintype "output"))
      (node (ref "IC6") (pin "3") (pinfunction "A_3") (pintype "input"))
    )
    (net (code "89") (name "Net-(IC12A-Q6)") (class "Default")
      (node (ref "IC12") (pin "13") (pinfunction "Q6_13") (pintype "output"))
      (node (ref "IC6") (pin "6") (pinfunction "B_6") (pintype "input"))
    )
    (net (code "90") (name "Net-(IC12A-Q7)") (class "Default")
      (node (ref "IC12") (pin "12") (pinfunction "Q7_12") (pintype "output"))
      (node (ref "IC6") (pin "7") (pinfunction "C_7") (pintype "input"))
    )
    (net (code "91") (name "Net-(IC12A-Q8)") (class "Default")
      (node (ref "IC12") (pin "11") (pinfunction "Q8_11") (pintype "output"))
      (node (ref "IC6") (pin "4") (pinfunction "D_4") (pintype "input"))
    )
    (net (code "92") (name "Net-(IC13A-Q1)") (class "Default")
      (node (ref "IC13") (pin "4") (pinfunction "Q1_4") (pintype "output"))
      (node (ref "IC2") (pin "3") (pinfunction "A_3") (pintype "input"))
    )
    (net (code "93") (name "Net-(IC13A-Q2)") (class "Default")
      (node (ref "IC13") (pin "5") (pinfunction "Q2_5") (pintype "output"))
      (node (ref "IC2") (pin "6") (pinfunction "B_6") (pintype "input"))
    )
    (net (code "94") (name "Net-(IC13A-Q3)") (class "Default")
      (node (ref "IC13") (pin "6") (pinfunction "Q3_6") (pintype "output"))
      (node (ref "IC2") (pin "7") (pinfunction "C_7") (pintype "input"))
    )
    (net (code "95") (name "Net-(IC13A-Q4)") (class "Default")
      (node (ref "IC13") (pin "7") (pinfunction "Q4_7") (pintype "output"))
      (node (ref "IC2") (pin "4") (pinfunction "D_4") (pintype "input"))
    )
    (net (code "96") (name "Net-(IC13A-Q5)") (class "Default")
      (node (ref "IC13") (pin "14") (pinfunction "Q5_14") (pintype "output"))
      (node (ref "IC3") (pin "3") (pinfunction "A_3") (pintype "input"))
    )
    (net (code "97") (name "Net-(IC13A-Q6)") (class "Default")
      (node (ref "IC13") (pin "13") (pinfunction "Q6_13") (pintype "output"))
      (node (ref "IC3") (pin "6") (pinfunction "B_6") (pintype "input"))
    )
    (net (code "98") (name "Net-(IC13A-Q7)") (class "Default")
      (node (ref "IC13") (pin "12") (pinfunction "Q7_12") (pintype "output"))
      (node (ref "IC3") (pin "7") (pinfunction "C_7") (pintype "input"))
    )
    (net (code "99") (name "Net-(IC13A-Q8)") (class "Default")
      (node (ref "IC13") (pin "11") (pinfunction "Q8_11") (pintype "output"))
      (node (ref "IC3") (pin "4") (pinfunction "D_4") (pintype "input"))
    )
    (net (code "100") (name "Net-(IC14A-Q1)") (class "Default")
      (node (ref "IC14") (pin "4") (pinfunction "Q1_4") (pintype "output"))
      (node (ref "IC7") (pin "3") (pinfunction "A_3") (pintype "input"))
    )
    (net (code "101") (name "Net-(IC14A-Q2)") (class "Default")
      (node (ref "IC14") (pin "5") (pinfunction "Q2_5") (pintype "output"))
      (node (ref "IC7") (pin "6") (pinfunction "B_6") (pintype "input"))
    )
    (net (code "102") (name "Net-(IC14A-Q3)") (class "Default")
      (node (ref "IC14") (pin "6") (pinfunction "Q3_6") (pintype "output"))
      (node (ref "IC7") (pin "7") (pinfunction "C_7") (pintype "input"))
    )
    (net (code "103") (name "Net-(IC14A-Q4)") (class "Default")
      (node (ref "IC14") (pin "7") (pinfunction "Q4_7") (pintype "output"))
      (node (ref "IC7") (pin "4") (pinfunction "D_4") (pintype "input"))
    )
    (net (code "104") (name "Net-(IC14A-Q5)") (class "Default")
      (node (ref "IC14") (pin "14") (pinfunction "Q5_14") (pintype "output"))
      (node (ref "IC8") (pin "3") (pinfunction "A_3") (pintype "input"))
    )
    (net (code "105") (name "Net-(IC14A-Q6)") (class "Default")
      (node (ref "IC14") (pin "13") (pinfunction "Q6_13") (pintype "output"))
      (node (ref "IC8") (pin "6") (pinfunction "B_6") (pintype "input"))
    )
    (net (code "106") (name "Net-(IC14A-Q7)") (class "Default")
      (node (ref "IC14") (pin "12") (pinfunction "Q7_12") (pintype "output"))
      (node (ref "IC8") (pin "7") (pinfunction "C_7") (pintype "input"))
    )
    (net (code "107") (name "Net-(IC14A-Q8)") (class "Default")
      (node (ref "IC14") (pin "11") (pinfunction "Q8_11") (pintype "output"))
      (node (ref "IC8") (pin "4") (pinfunction "D_4") (pintype "input"))
    )
    (net (code "108") (name "Net-(PAD1-P)") (class "Default")
      (node (ref "PAD1") (pin "1") (pinfunction "P_1") (pintype "passive"))
      (node (ref "R13") (pin "1") (pinfunction "1_1") (pintype "passive"))
    )
    (net (code "109") (name "Net-(PAD2-P)") (class "Default")
      (node (ref "PAD2") (pin "1") (pinfunction "P_1") (pintype "passive"))
      (node (ref "R9") (pin "1") (pinfunction "1_1") (pintype "passive"))
    )
    (net (code "110") (name "Net-(PAD3-P)") (class "Default")
      (node (ref "PAD3") (pin "1") (pinfunction "P_1") (pintype "passive"))
      (node (ref "R12") (pin "1") (pinfunction "1_1") (pintype "passive"))
    )
    (net (code "111") (name "Net-(PAD4-P)") (class "Default")
      (node (ref "PAD4") (pin "1") (pinfunction "P_1") (pintype "passive"))
      (node (ref "R5") (pin "1") (pinfunction "1_1") (pintype "passive"))
    )
    (net (code "112") (name "Net-(PAD5-P)") (class "Default")
      (node (ref "PAD5") (pin "1") (pinfunction "P_1") (pintype "passive"))
      (node (ref "R4") (pin "1") (pinfunction "1_1") (pintype "passive"))
    )
    (net (code "113") (name "Net-(PAD6-P)") (class "Default")
      (node (ref "PAD6") (pin "1") (pinfunction "P_1") (pintype "passive"))
      (node (ref "R11") (pin "1") (pinfunction "1_1") (pintype "passive"))
    )
    (net (code "114") (name "Net-(Q1-D)") (class "Default")
      (node (ref "D3") (pin "A") (pinfunction "A_A") (pintype "passive"))
      (node (ref "L1") (pin "1") (pinfunction "1_1") (pintype "passive"))
      (node (ref "Q1") (pin "2") (pinfunction "D_2") (pintype "bidirectional"))
      (node (ref "R10") (pin "2") (pinfunction "2_2") (pintype "passive"))
    )
    (net (code "115") (name "Net-(R8-E)") (class "Default")
      (node (ref "R6") (pin "1") (pinfunction "1_1") (pintype "passive"))
      (node (ref "R8") (pin "3") (pinfunction "E_3") (pintype "passive"))
    )
    (net (code "116") (name "Net-(R8-S)") (class "Default")
      (node (ref "R7") (pin "2") (pinfunction "2_2") (pintype "passive"))
      (node (ref "R8") (pin "2") (pinfunction "S_2") (pintype "passive"))
      (node (ref "T1") (pin "2") (pinfunction "B_2") (pintype "passive"))
    )
    (net (code "117") (name "VCC") (class "Default")
      (node (ref "C4") (pin "+") (pinfunction "+_+") (pintype "passive"))
      (node (ref "CN1") (pin "PWR") (pinfunction "PWR_PWR") (pintype "power_in"))
      (node (ref "IC1") (pin "8") (pinfunction "V+_8") (pintype "power_in"))
      (node (ref "IC4") (pin "1") (pinfunction "VI_1") (pintype "input"))
      (node (ref "L1") (pin "2") (pinfunction "2_2") (pintype "passive"))
      (node (ref "R14") (pin "2") (pinfunction "2_2") (pintype "passive"))
    )
    (net (code "118") (name "unconnected-(IC12A-QS*-Pad10)") (class "Default")
      (node (ref "IC12") (pin "10") (pinfunction "QS*_10") (pintype "output"))
    )
    (net (code "119") (name "unconnected-(IC12A-QS-Pad9)") (class "Default")
      (node (ref "IC12") (pin "9") (pinfunction "QS_9") (pintype "output"))
    )
    (net (code "120") (name "unconnected-(IC13A-QS*-Pad10)") (class "Default")
      (node (ref "IC13") (pin "10") (pinfunction "QS*_10") (pintype "output"))
    )
    (net (code "121") (name "unconnected-(IC13A-QS-Pad9)") (class "Default")
      (node (ref "IC13") (pin "9") (pinfunction "QS_9") (pintype "output"))
    )
    (net (code "122") (name "unconnected-(IC14A-QS*-Pad10)") (class "Default")
      (node (ref "IC14") (pin "10") (pinfunction "QS*_10") (pintype "output"))
    )
    (net (code "123") (name "unconnected-(IC14A-QS-Pad9)") (class "Default")
      (node (ref "IC14") (pin "9") (pinfunction "QS_9") (pintype "output"))
    )
    (net (code "124") (name "unconnected-(R8-A-Pad1)") (class "Default")
      (node (ref "R8") (pin "1") (pinfunction "A_1") (pintype "passive"))
    )
    (net (code "125") (name "unconnected-(U$1-0-PadP$25)") (class "Default")
      (node (ref "U$1") (pin "P$25") (pinfunction "0_P$25") (pintype "bidirectional"))
    )
    (net (code "126") (name "unconnected-(U$1-1-PadP$35)") (class "Default")
      (node (ref "U$1") (pin "P$35") (pinfunction "1_P$35") (pintype "bidirectional"))
    )
    (net (code "127") (name "unconnected-(U$1-2-PadP$24)") (class "Default")
      (node (ref "U$1") (pin "P$24") (pinfunction "2_P$24") (pintype "bidirectional"))
    )
    (net (code "128") (name "unconnected-(U$1-3-PadP$34)") (class "Default")
      (node (ref "U$1") (pin "P$34") (pinfunction "3_P$34") (pintype "bidirectional"))
    )
    (net (code "129") (name "unconnected-(U$1-4-PadP$26)") (class "Default")
      (node (ref "U$1") (pin "P$26") (pinfunction "4_P$26") (pintype "bidirectional"))
    )
    (net (code "130") (name "unconnected-(U$1-5-PadP$29)") (class "Default")
      (node (ref "U$1") (pin "P$29") (pinfunction "5_P$29") (pintype "bidirectional"))
    )
    (net (code "131") (name "unconnected-(U$1-6-PadP$20)") (class "Default")
      (node (ref "U$1") (pin "P$20") (pinfunction "6_P$20") (pintype "bidirectional"))
    )
    (net (code "132") (name "unconnected-(U$1-7-PadP$21)") (class "Default")
      (node (ref "U$1") (pin "P$21") (pinfunction "7_P$21") (pintype "bidirectional"))
    )
    (net (code "133") (name "unconnected-(U$1-8-PadP$22)") (class "Default")
      (node (ref "U$1") (pin "P$22") (pinfunction "8_P$22") (pintype "bidirectional"))
    )
    (net (code "134") (name "unconnected-(U$1-9-PadP$16)") (class "Default")
      (node (ref "U$1") (pin "P$16") (pinfunction "9_P$16") (pintype "bidirectional"))
    )
    (net (code "135") (name "unconnected-(U$1-10-PadP$17)") (class "Default")
      (node (ref "U$1") (pin "P$17") (pinfunction "10_P$17") (pintype "bidirectional"))
    )
    (net (code "136") (name "unconnected-(U$1-11-PadP$18)") (class "Default")
      (node (ref "U$1") (pin "P$18") (pinfunction "11_P$18") (pintype "bidirectional"))
    )
    (net (code "137") (name "unconnected-(U$1-15-PadP$23)") (class "Default")
      (node (ref "U$1") (pin "P$23") (pinfunction "15_P$23") (pintype "bidirectional"))
    )
    (net (code "138") (name "unconnected-(U$1-16-PadP$27)") (class "Default")
      (node (ref "U$1") (pin "P$27") (pinfunction "16_P$27") (pintype "bidirectional"))
    )
    (net (code "139") (name "unconnected-(U$1-17-PadP$28)") (class "Default")
      (node (ref "U$1") (pin "P$28") (pinfunction "17_P$28") (pintype "bidirectional"))
    )
    (net (code "140") (name "unconnected-(U$1-18-PadP$30)") (class "Default")
      (node (ref "U$1") (pin "P$30") (pinfunction "18_P$30") (pintype "bidirectional"))
    )
    (net (code "141") (name "unconnected-(U$1-19-PadP$31)") (class "Default")
      (node (ref "U$1") (pin "P$31") (pinfunction "19_P$31") (pintype "bidirectional"))
    )
    (net (code "142") (name "unconnected-(U$1-21-PadP$33)") (class "Default")
      (node (ref "U$1") (pin "P$33") (pinfunction "21_P$33") (pintype "bidirectional"))
    )
    (net (code "143") (name "unconnected-(U$1-22-PadP$36)") (class "Default")
      (node (ref "U$1") (pin "P$36") (pinfunction "22_P$36") (pintype "bidirectional"))
    )
    (net (code "144") (name "unconnected-(U$1-23-PadP$37)") (class "Default")
      (node (ref "U$1") (pin "P$37") (pinfunction "23_P$37") (pintype "bidirectional"))
    )
    (net (code "145") (name "unconnected-(U$1-EN-PadP$2)") (class "Default")
      (node (ref "U$1") (pin "P$2") (pinfunction "EN_P$2") (pintype "bidirectional"))
    )
  )
)
